# triple_diode_v1.net
KiCad netlist of a schematic drawn in EasyEDA Pro
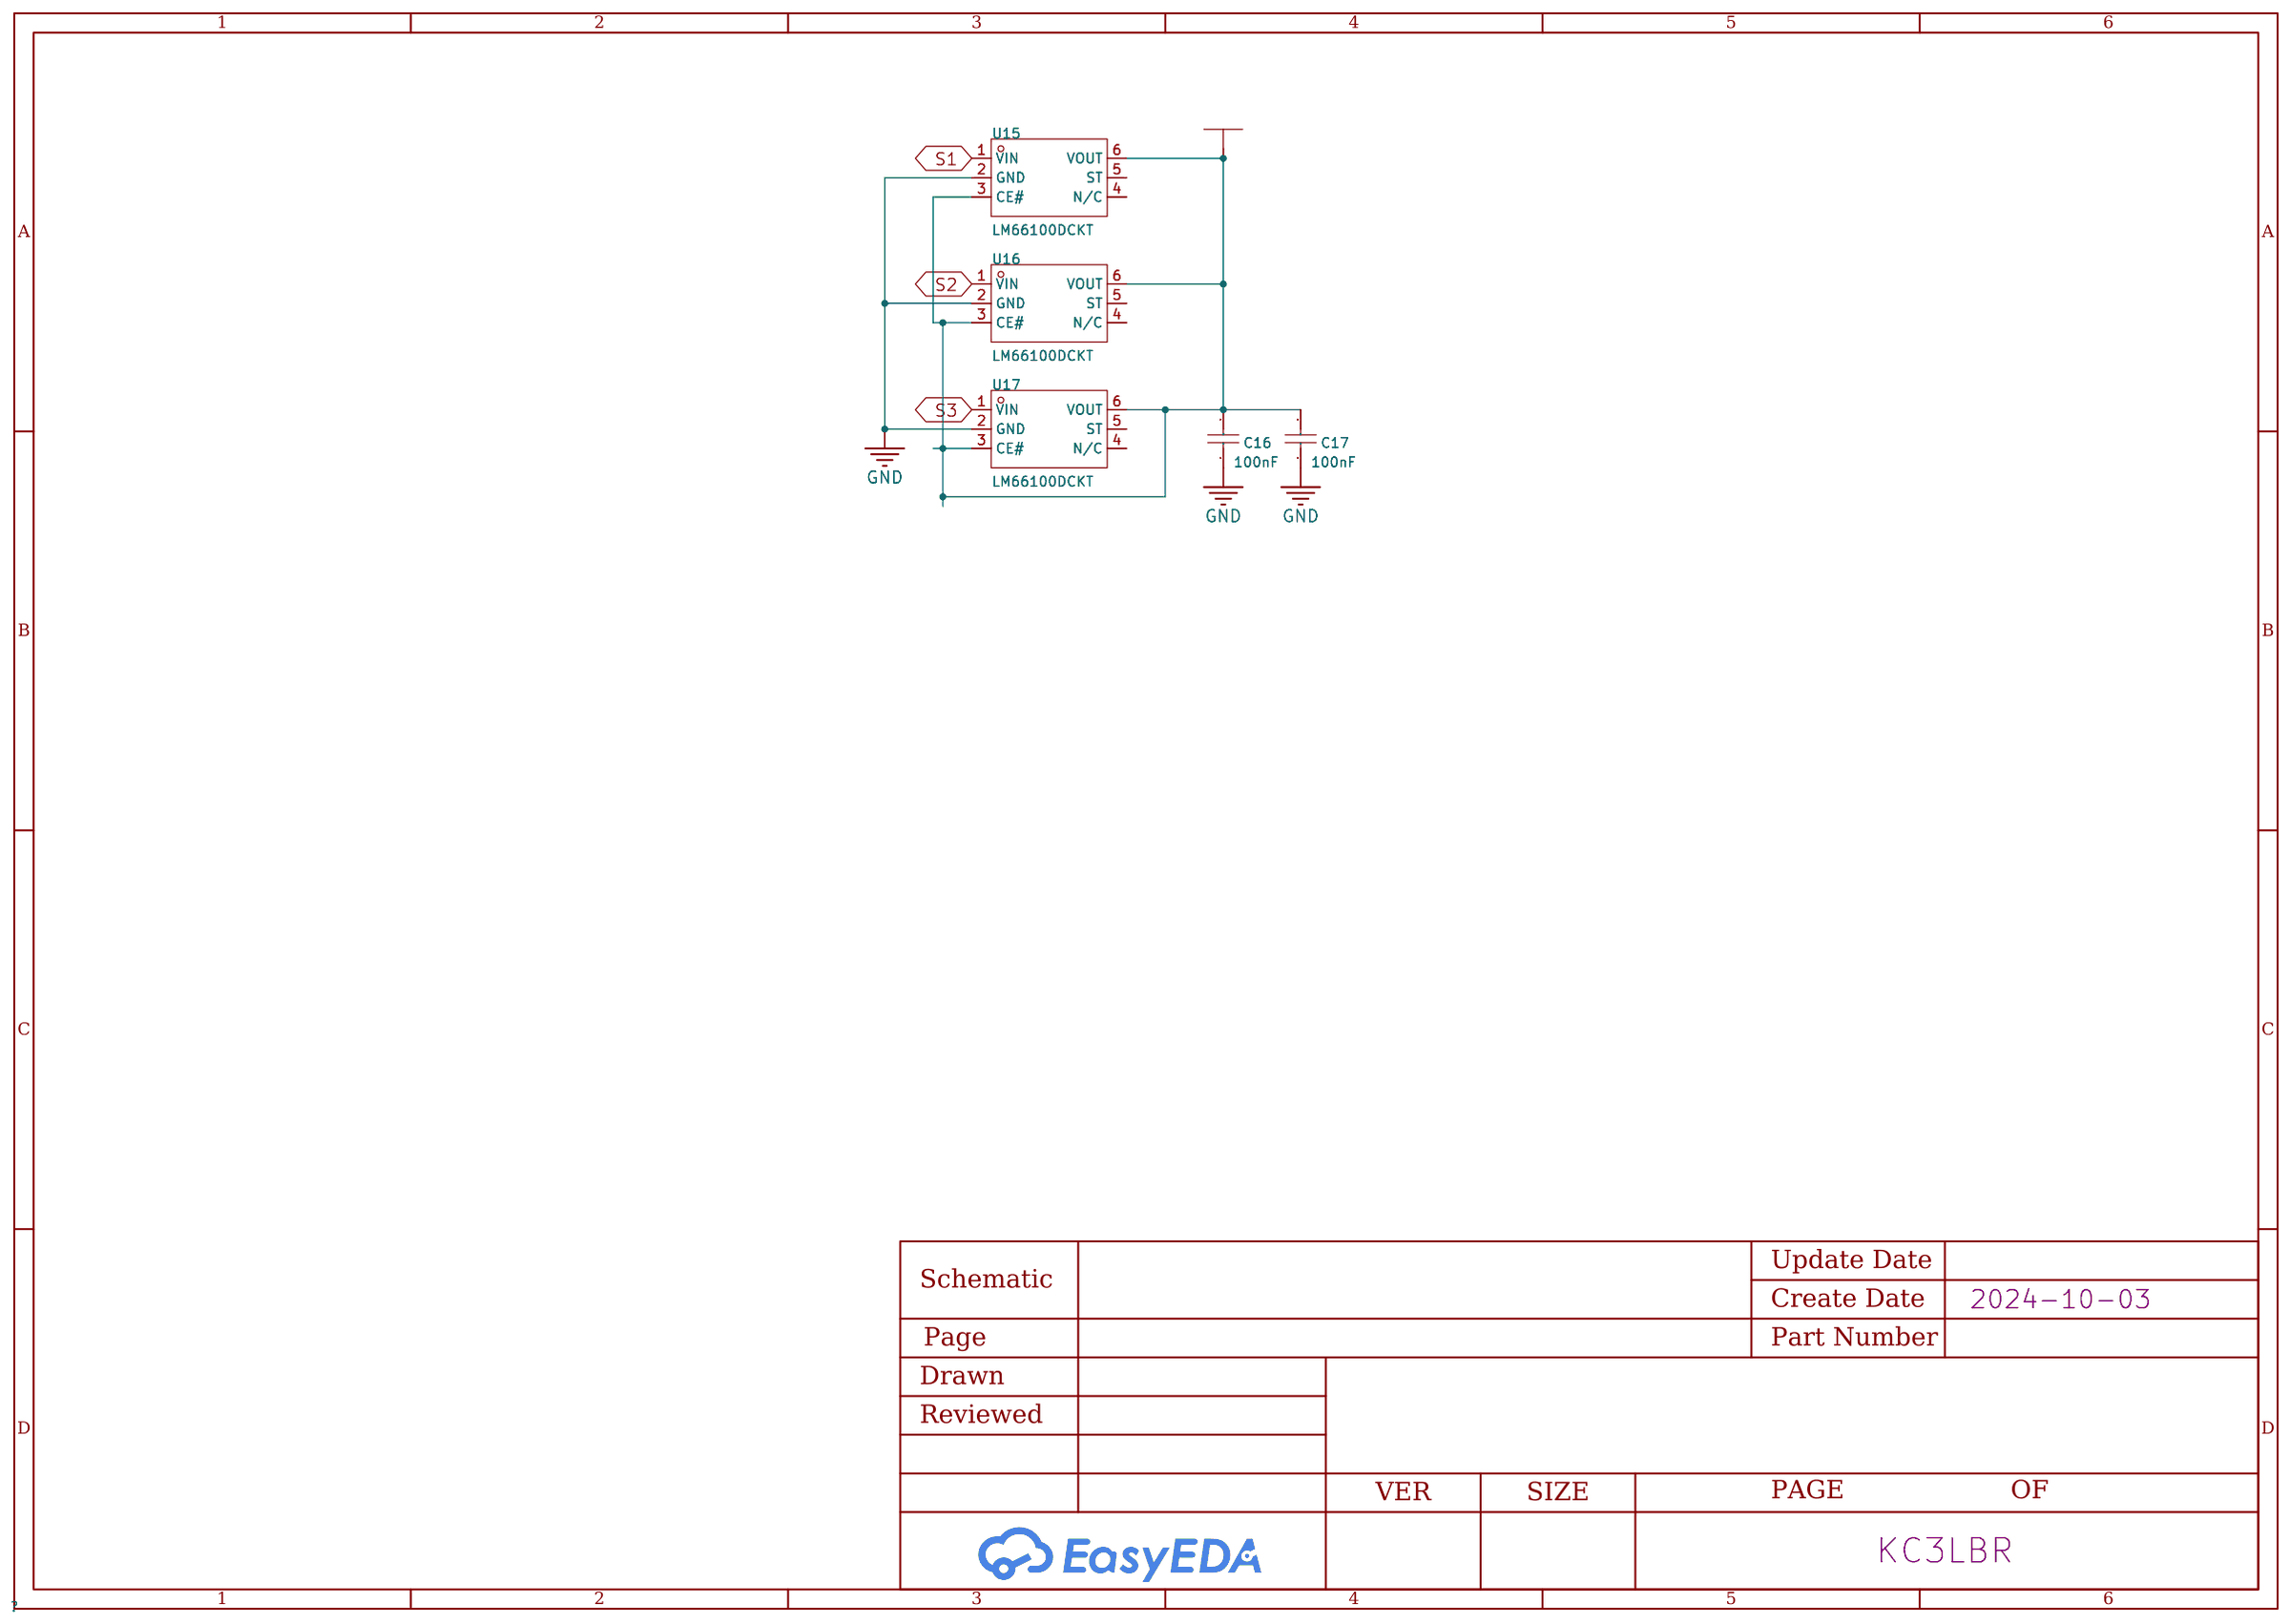
[diagram p0: schematic sheet]

(export (version "E")
  (design (tool "Eeschema 10.0.6"))
  (components
    (comp (ref "C16")
      (value "100nF")
      (footprint "easyedapro:C0402_NEW")
      (fields
        (field (name "Manufacturer Part") "CL05B104KO5NNNC")
        (field (name "Manufacturer") "SAMSUNG(三星)")
      )
      (libsource (lib "easyedapro") (part "CL05B104KO5NNNC"))
    )
    (comp (ref "C17")
      (value "100nF")
      (footprint "easyedapro:C0402_NEW")
      (fields
        (field (name "Manufacturer Part") "CL05B104KO5NNNC")
        (field (name "Manufacturer") "SAMSUNG(三星)")
      )
      (libsource (lib "easyedapro") (part "CL05B104KO5NNNC"))
    )
    (comp (ref "U15")
      (value "LM66100DCKT")
      (footprint "easyedapro:SC-70-6_L2.0-W1.3-P0.65-LS2.1-BL")
      (fields (field (name "Manufacturer") "TI(德州仪器)"))
      (libsource (lib "easyedapro") (part "LM66100DCKT"))
    )
    (comp (ref "U16")
      (value "LM66100DCKT")
      (footprint "easyedapro:SC-70-6_L2.0-W1.3-P0.65-LS2.1-BL")
      (fields (field (name "Manufacturer") "TI(德州仪器)"))
      (libsource (lib "easyedapro") (part "LM66100DCKT"))
    )
    (comp (ref "U17")
      (value "LM66100DCKT")
      (footprint "easyedapro:SC-70-6_L2.0-W1.3-P0.65-LS2.1-BL")
      (fields (field (name "Manufacturer") "TI(德州仪器)"))
      (libsource (lib "easyedapro") (part "LM66100DCKT"))
    )
  )
  (nets
    (net (code "1") (name "GND") (class "Default")
      (node (ref "C16") (pin "1") (pinfunction "1_1") (pintype "input"))
      (node (ref "C17") (pin "1") (pinfunction "1_1") (pintype "input"))
      (node (ref "U15") (pin "2") (pinfunction "GND_2") (pintype "input"))
      (node (ref "U16") (pin "2") (pinfunction "GND_2") (pintype "input"))
      (node (ref "U17") (pin "2") (pinfunction "GND_2") (pintype "input"))
    )
    (net (code "2") (name "S1") (class "Default")
      (node (ref "U15") (pin "1") (pinfunction "VIN_1") (pintype "input"))
    )
    (net (code "3") (name "S2") (class "Default")
      (node (ref "U16") (pin "1") (pinfunction "VIN_1") (pintype "input"))
    )
    (net (code "4") (name "S3") (class "Default")
      (node (ref "U17") (pin "1") (pinfunction "VIN_1") (pintype "input"))
    )
    (net (code "5") (name "VBUS") (class "Default")
      (node (ref "C16") (pin "2") (pinfunction "2_2") (pintype "input"))
      (node (ref "C17") (pin "2") (pinfunction "2_2") (pintype "input"))
      (node (ref "U15") (pin "3") (pinfunction "CE#_3") (pintype "input"))
      (node (ref "U15") (pin "6") (pinfunction "VOUT_6") (pintype "input"))
      (node (ref "U16") (pin "3") (pinfunction "CE#_3") (pintype "input"))
      (node (ref "U16") (pin "6") (pinfunction "VOUT_6") (pintype "input"))
      (node (ref "U17") (pin "3") (pinfunction "CE#_3") (pintype "input"))
      (node (ref "U17") (pin "6") (pinfunction "VOUT_6") (pintype "input"))
    )
    (net (code "6") (name "unconnected-(U15-N{slash}C-Pad4)") (class "Default")
      (node (ref "U15") (pin "4") (pinfunction "N/C_4") (pintype "input"))
    )
    (net (code "7") (name "unconnected-(U15-ST-Pad5)") (class "Default")
      (node (ref "U15") (pin "5") (pinfunction "ST_5") (pintype "input"))
    )
    (net (code "8") (name "unconnected-(U16-N{slash}C-Pad4)") (class "Default")
      (node (ref "U16") (pin "4") (pinfunction "N/C_4") (pintype "input"))
    )
    (net (code "9") (name "unconnected-(U16-ST-Pad5)") (class "Default")
      (node (ref "U16") (pin "5") (pinfunction "ST_5") (pintype "input"))
    )
    (net (code "10") (name "unconnected-(U17-N{slash}C-Pad4)") (class "Default")
      (node (ref "U17") (pin "4") (pinfunction "N/C_4") (pintype "input"))
    )
    (net (code "11") (name "unconnected-(U17-ST-Pad5)") (class "Default")
      (node (ref "U17") (pin "5") (pinfunction "ST_5") (pintype "input"))
    )
  )
)
